# ai_breakout_tb6612fng.net
KiCad netlist of a schematic drawn in EAGLE
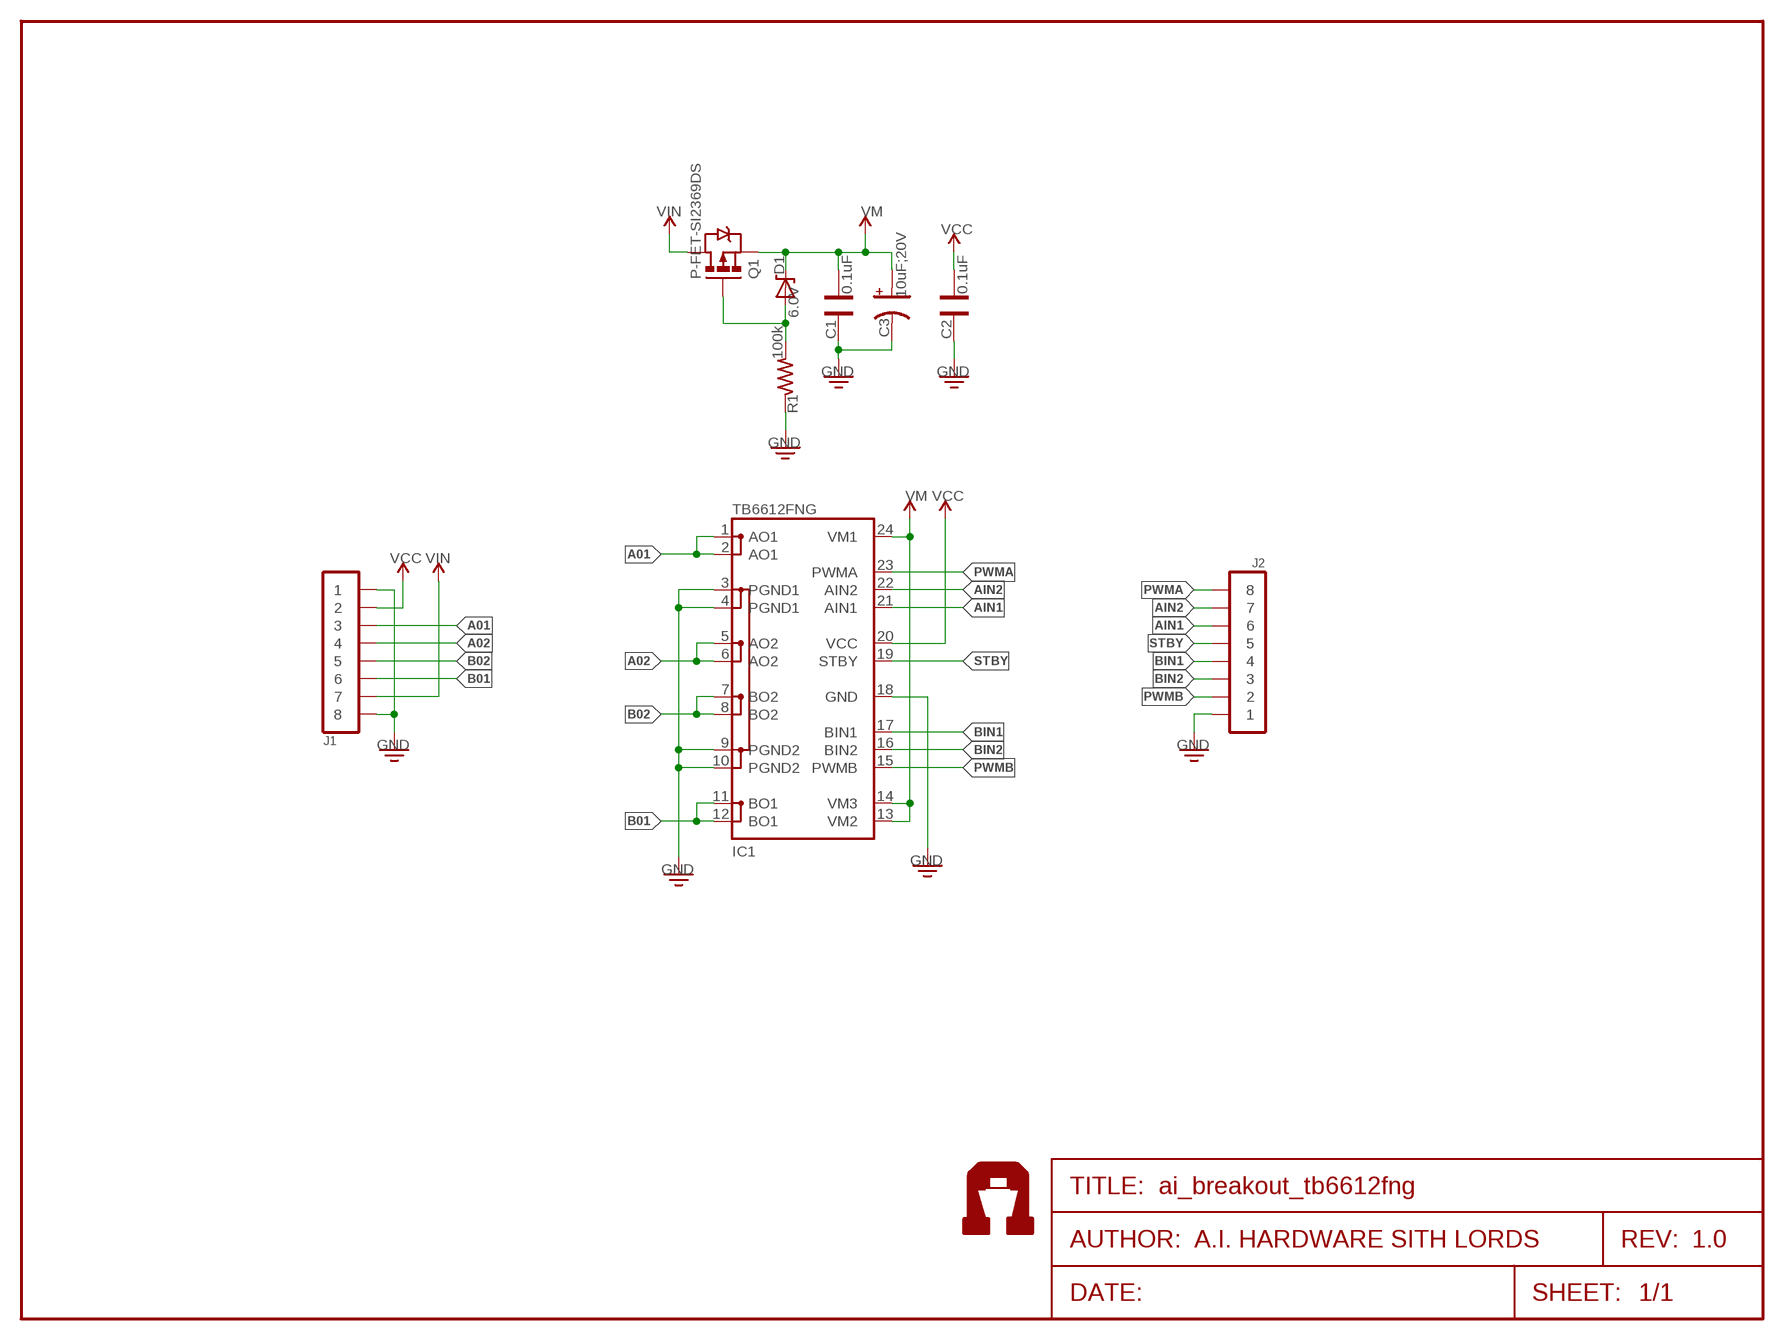
[diagram p0: schematic, sheet 1]

(export (version "E")
  (design (tool "Eeschema 10.0.6"))
  (components
    (comp (ref "C1")
      (value "0.1uF")
      (footprint "eagle-import:CAP-0603")
      (libsource (lib "eagle-import") (part "CAP0603"))
    )
    (comp (ref "C2")
      (value "0.1uF")
      (footprint "eagle-import:CAP-0603")
      (libsource (lib "eagle-import") (part "CAP0603"))
    )
    (comp (ref "C3")
      (value "10uF;20V")
      (footprint "eagle-import:CAP-POL-EIA3216")
      (libsource (lib "eagle-import") (part "CAP-POLEIA3216"))
    )
    (comp (ref "D1")
      (value "6.0V")
      (footprint "eagle-import:SOD-323")
      (libsource (lib "eagle-import") (part "DIODE-ZENER-BZT52"))
    )
    (comp (ref "IC1")
      (value "TB6612FNG")
      (footprint "eagle-import:SSOP24")
      (libsource (lib "eagle-import") (part "TB6612FNG"))
    )
    (comp (ref "J1")
      (value "1X08")
      (footprint "eagle-import:1X08")
      (libsource (lib "eagle-import") (part "1X08"))
    )
    (comp (ref "J2")
      (value "1X08NOFIRST")
      (footprint "eagle-import:1X08-NOFIRST")
      (libsource (lib "eagle-import") (part "1X08NOFIRST"))
    )
    (comp (ref "Q1")
      (value "P-FET-SI2369DS")
      (footprint "eagle-import:SOT-23")
      (libsource (lib "eagle-import") (part "P-FET-SI2369DS"))
    )
    (comp (ref "R1")
      (value "100k")
      (footprint "eagle-import:RES-0603")
      (libsource (lib "eagle-import") (part "RES0603"))
    )
    (comp (ref "U$5")
      (value "AI-LOGOXS")
      (footprint "eagle-import:AI-LOGO-XS")
      (libsource (lib "eagle-import") (part "AI-LOGOXS"))
    )
  )
  (nets
    (net (code "1") (name "A01") (class "Default")
      (node (ref "IC1") (pin "1") (pinfunction "AO1_1") (pintype "open_collector"))
      (node (ref "IC1") (pin "2") (pinfunction "AO1_2") (pintype "open_collector"))
      (node (ref "J1") (pin "3") (pinfunction "3_3") (pintype "bidirectional"))
    )
    (net (code "2") (name "A02") (class "Default")
      (node (ref "IC1") (pin "5") (pinfunction "AO2_5") (pintype "open_collector"))
      (node (ref "IC1") (pin "6") (pinfunction "AO2_6") (pintype "open_collector"))
      (node (ref "J1") (pin "4") (pinfunction "4_4") (pintype "bidirectional"))
    )
    (net (code "3") (name "AIN1") (class "Default")
      (node (ref "IC1") (pin "21") (pinfunction "AIN1_21") (pintype "input"))
      (node (ref "J2") (pin "6") (pinfunction "6_6") (pintype "bidirectional"))
    )
    (net (code "4") (name "AIN2") (class "Default")
      (node (ref "IC1") (pin "22") (pinfunction "AIN2_22") (pintype "input"))
      (node (ref "J2") (pin "7") (pinfunction "7_7") (pintype "bidirectional"))
    )
    (net (code "5") (name "B01") (class "Default")
      (node (ref "IC1") (pin "11") (pinfunction "BO1_11") (pintype "open_collector"))
      (node (ref "IC1") (pin "12") (pinfunction "BO1_12") (pintype "open_collector"))
      (node (ref "J1") (pin "6") (pinfunction "6_6") (pintype "bidirectional"))
    )
    (net (code "6") (name "B02") (class "Default")
      (node (ref "IC1") (pin "7") (pinfunction "BO2_7") (pintype "open_collector"))
      (node (ref "IC1") (pin "8") (pinfunction "BO2_8") (pintype "open_collector"))
      (node (ref "J1") (pin "5") (pinfunction "5_5") (pintype "bidirectional"))
    )
    (net (code "7") (name "BIN1") (class "Default")
      (node (ref "IC1") (pin "17") (pinfunction "BIN1_17") (pintype "input"))
      (node (ref "J2") (pin "4") (pinfunction "4_4") (pintype "bidirectional"))
    )
    (net (code "8") (name "BIN2") (class "Default")
      (node (ref "IC1") (pin "16") (pinfunction "BIN2_16") (pintype "input"))
      (node (ref "J2") (pin "3") (pinfunction "3_3") (pintype "bidirectional"))
    )
    (net (code "9") (name "GND") (class "Default")
      (node (ref "C1") (pin "2") (pinfunction "2_2") (pintype "passive"))
      (node (ref "C2") (pin "2") (pinfunction "2_2") (pintype "passive"))
      (node (ref "C3") (pin "C") (pinfunction "C_C") (pintype "passive"))
      (node (ref "IC1") (pin "10") (pinfunction "PGND2_10") (pintype "power_in"))
      (node (ref "IC1") (pin "18") (pinfunction "GND_18") (pintype "power_in"))
      (node (ref "IC1") (pin "3") (pinfunction "PGND1_3") (pintype "power_in"))
      (node (ref "IC1") (pin "4") (pinfunction "PGND1_4") (pintype "power_in"))
      (node (ref "IC1") (pin "9") (pinfunction "PGND2_9") (pintype "power_in"))
      (node (ref "J1") (pin "1") (pinfunction "1_1") (pintype "bidirectional"))
      (node (ref "J1") (pin "8") (pinfunction "8_8") (pintype "bidirectional"))
      (node (ref "J2") (pin "1") (pinfunction "1_1") (pintype "bidirectional"))
      (node (ref "R1") (pin "1") (pinfunction "1_1") (pintype "passive"))
    )
    (net (code "10") (name "Net-(Q1-G)") (class "Default")
      (node (ref "D1") (pin "A") (pinfunction "A_A") (pintype "passive"))
      (node (ref "Q1") (pin "1") (pinfunction "G_1") (pintype "passive"))
      (node (ref "R1") (pin "2") (pinfunction "2_2") (pintype "passive"))
    )
    (net (code "11") (name "PWMA") (class "Default")
      (node (ref "IC1") (pin "23") (pinfunction "PWMA_23") (pintype "input"))
      (node (ref "J2") (pin "8") (pinfunction "8_8") (pintype "bidirectional"))
    )
    (net (code "12") (name "PWMB") (class "Default")
      (node (ref "IC1") (pin "15") (pinfunction "PWMB_15") (pintype "input"))
      (node (ref "J2") (pin "2") (pinfunction "2_2") (pintype "bidirectional"))
    )
    (net (code "13") (name "STBY") (class "Default")
      (node (ref "IC1") (pin "19") (pinfunction "STBY_19") (pintype "input"))
      (node (ref "J2") (pin "5") (pinfunction "5_5") (pintype "bidirectional"))
    )
    (net (code "14") (name "VCC") (class "Default")
      (node (ref "C2") (pin "1") (pinfunction "1_1") (pintype "passive"))
      (node (ref "IC1") (pin "20") (pinfunction "VCC_20") (pintype "power_in"))
      (node (ref "J1") (pin "2") (pinfunction "2_2") (pintype "bidirectional"))
    )
    (net (code "15") (name "VIN") (class "Default")
      (node (ref "J1") (pin "7") (pinfunction "7_7") (pintype "bidirectional"))
      (node (ref "Q1") (pin "3") (pinfunction "D_3") (pintype "passive"))
    )
    (net (code "16") (name "VM") (class "Default")
      (node (ref "C1") (pin "1") (pinfunction "1_1") (pintype "passive"))
      (node (ref "C3") (pin "A") (pinfunction "A_A") (pintype "passive"))
      (node (ref "D1") (pin "C") (pinfunction "C_C") (pintype "passive"))
      (node (ref "IC1") (pin "13") (pinfunction "VM2_13") (pintype "power_in"))
      (node (ref "IC1") (pin "14") (pinfunction "VM3_14") (pintype "power_in"))
      (node (ref "IC1") (pin "24") (pinfunction "VM1_24") (pintype "power_in"))
      (node (ref "Q1") (pin "2") (pinfunction "S_2") (pintype "passive"))
    )
  )
)
